# MainBoard_Top.net
KiCad netlist of a schematic drawn in Altium Designer
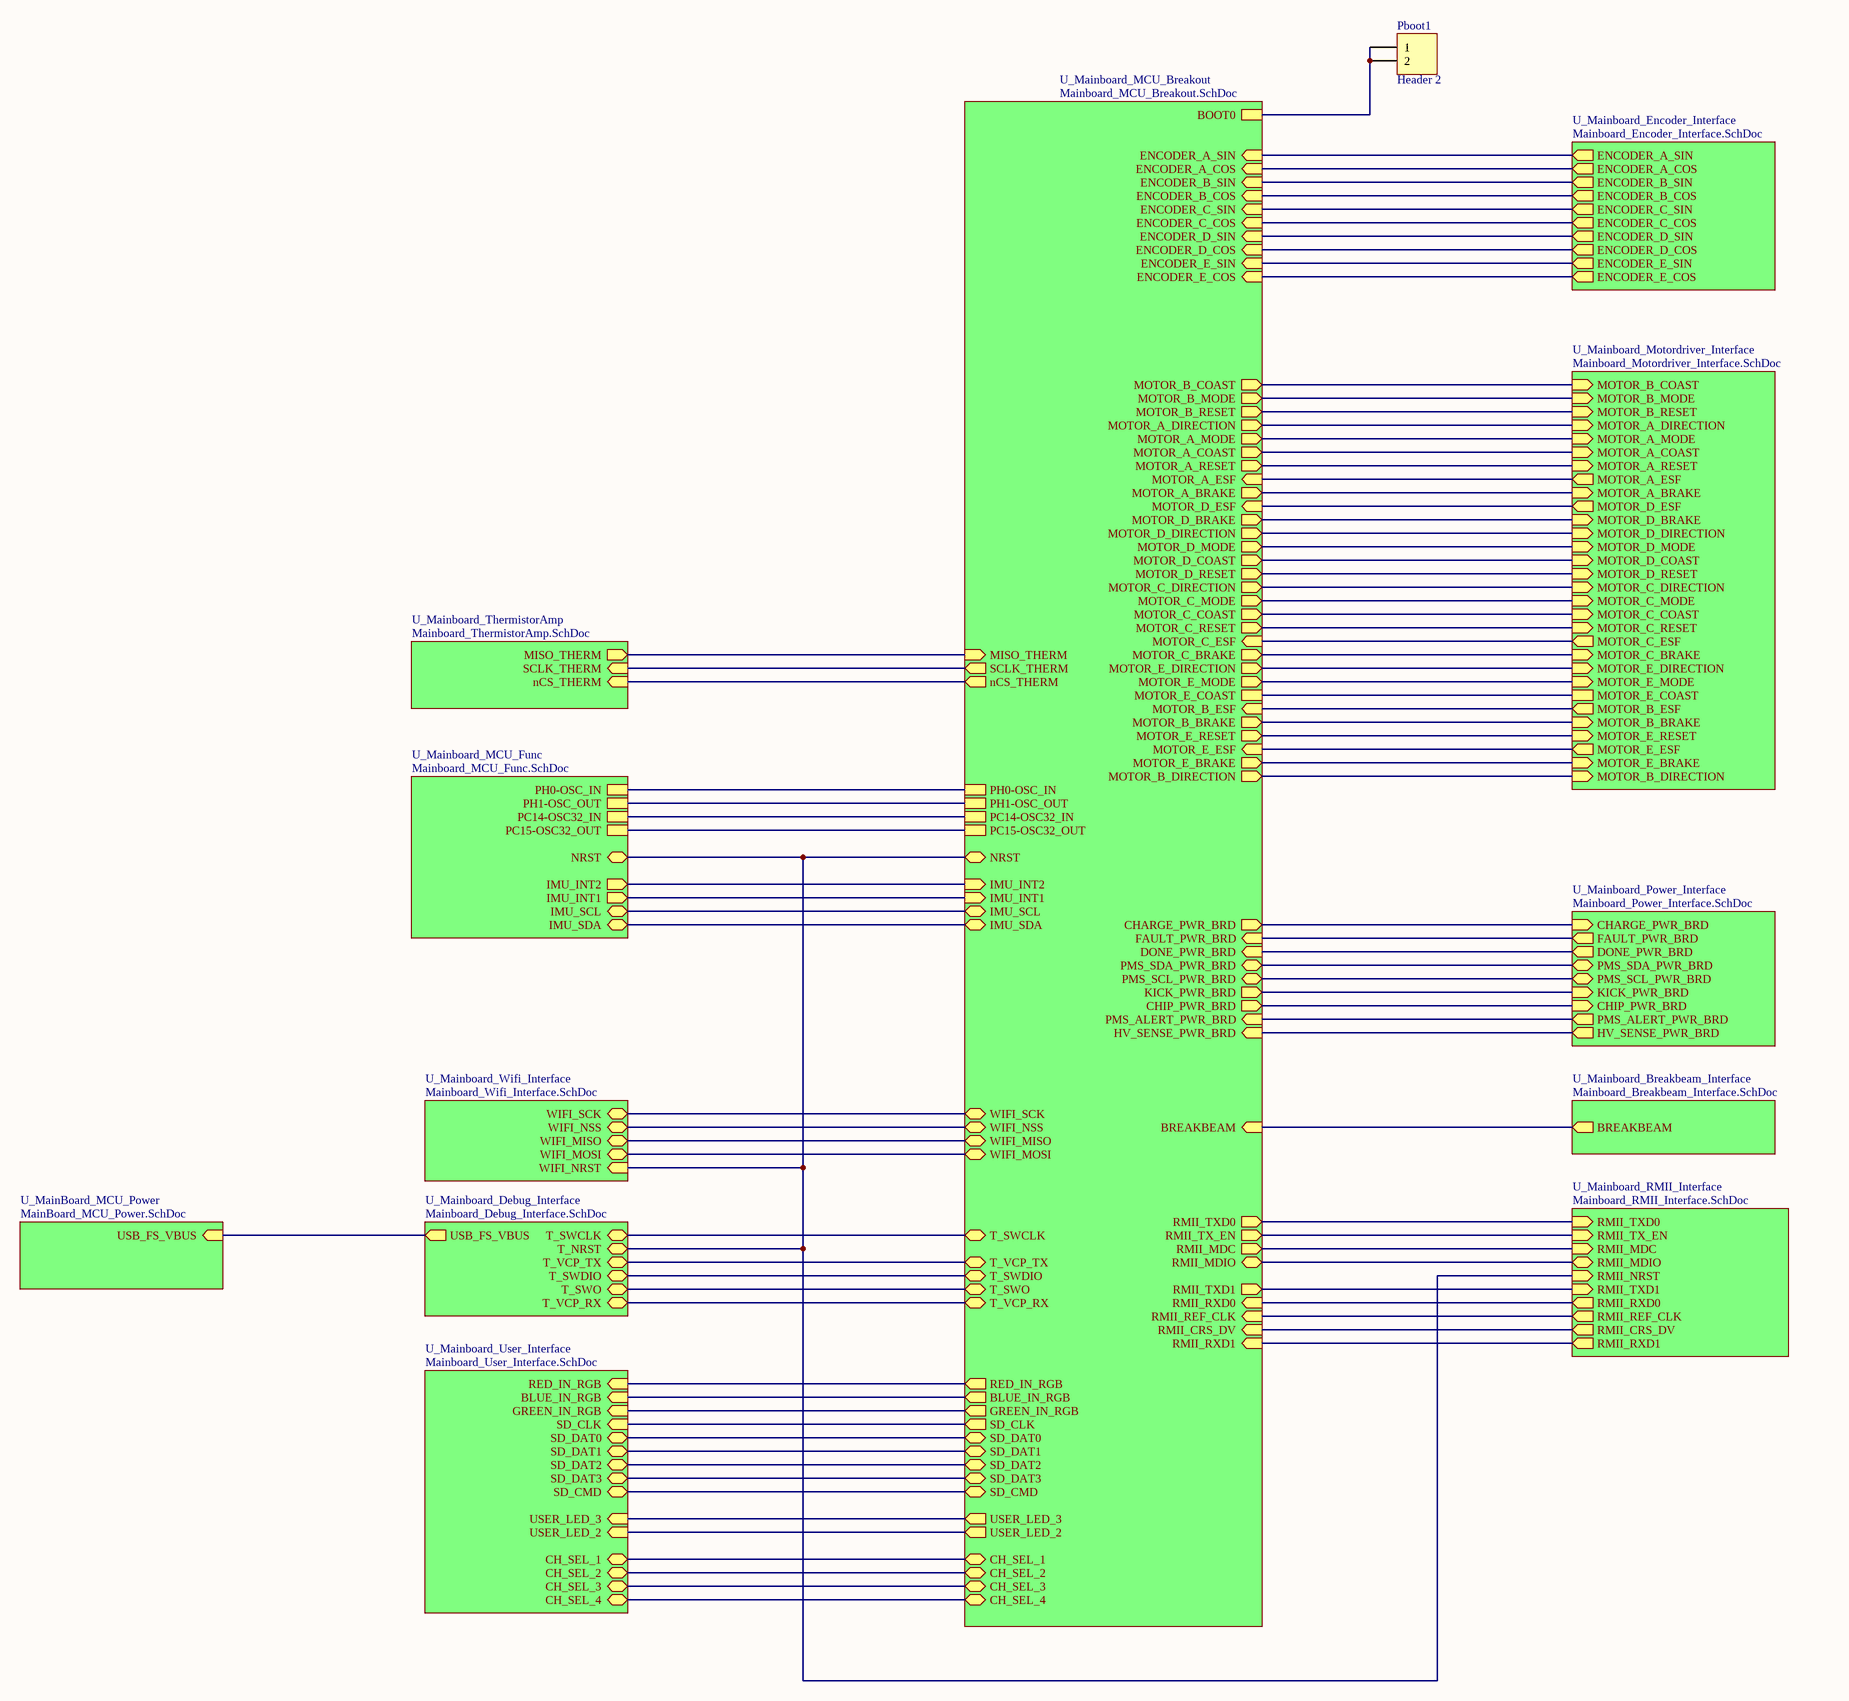
[diagram p0: MainBoard_Top.SchDoc]

(export (version "E")
  (design (tool "Eeschema 10.0.6"))
  (components
    (comp (ref "Pboot1")
      (value "Header 2")
      (footprint "HDR1X2")
      (description "Header, 2-Pin")
      (fields (field (name "PUBLISHER") "Altium Limited"))
      (libsource (lib "Miscellaneous Connectors") (part "Header 2"))
    )
  )
  (nets
    (net (code "2") (name "/BOOT0") (class "Default")
      (node (ref "Pboot1") (pin "1") (pinfunction "1_1") (pintype "passive"))
      (node (ref "Pboot1") (pin "2") (pinfunction "2_2") (pintype "passive"))
    )
  )
)
